# ife18_TS_BMS_Master.net
KiCad netlist of a schematic drawn in Altium Designer
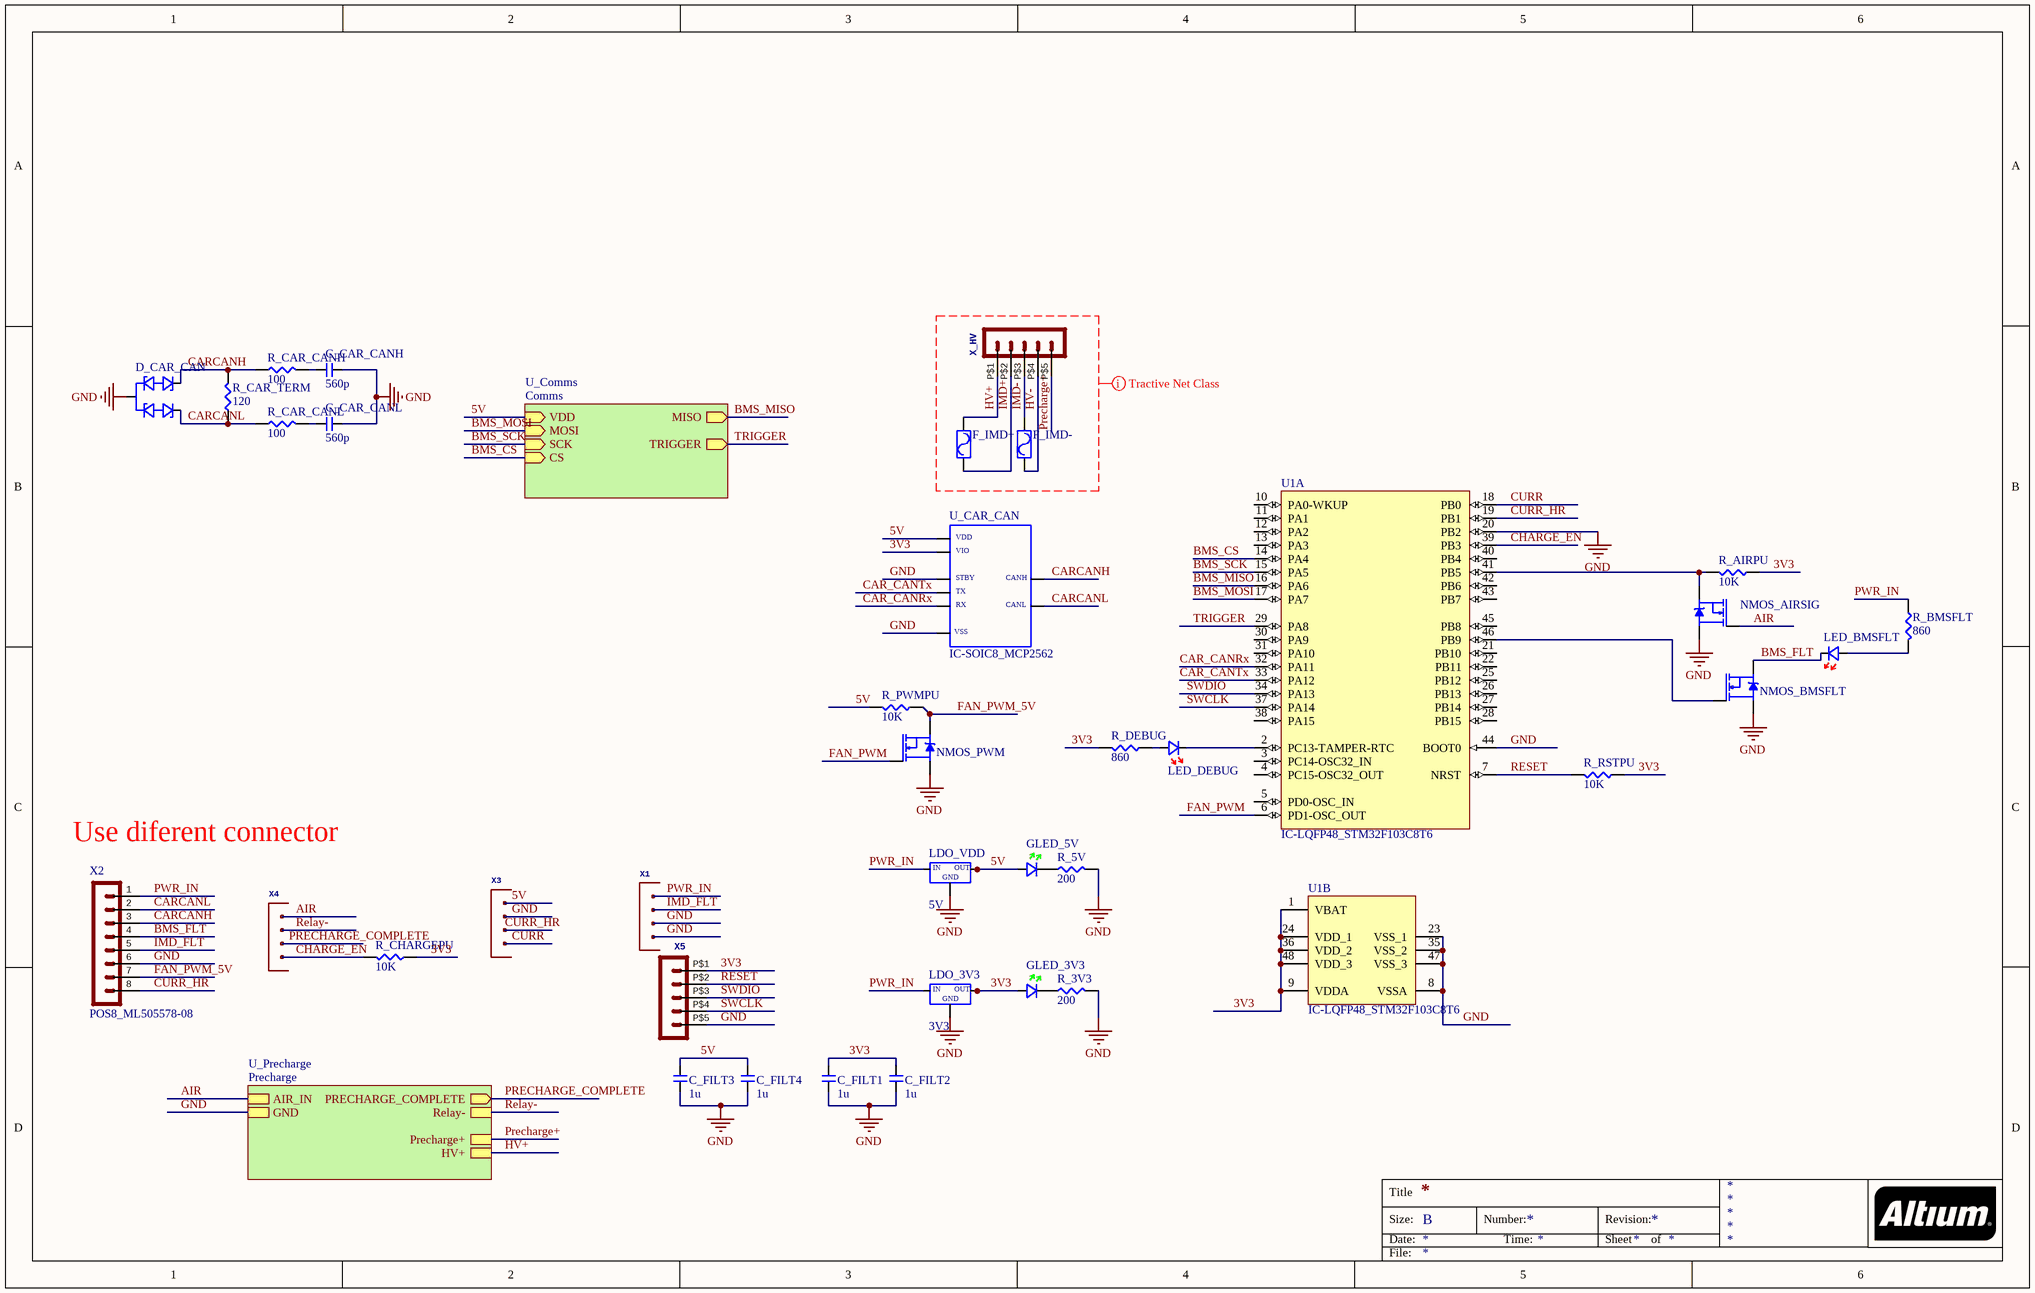
[diagram p0: ife18_TS_BMS_Master.SchDoc]

(export (version "E")
  (design (tool "Eeschema 10.0.6"))
  (components
    (comp (ref "C_CAR_CANH")
      (value "560p")
      (footprint "CAP-0603")
      (libsource (lib "altium-import") (part "root_0_CAP-0603_"))
    )
    (comp (ref "C_CAR_CANL")
      (value "560p")
      (footprint "CAP-0603")
      (libsource (lib "altium-import") (part "root_0_CAP-0603_"))
    )
    (comp (ref "C_FILT1")
      (value "1u")
      (footprint "CAP-0603")
      (libsource (lib "altium-import") (part "root_1_CAP-0603_"))
    )
    (comp (ref "C_FILT2")
      (value "1u")
      (footprint "CAP-0603")
      (libsource (lib "altium-import") (part "root_1_CAP-0603_"))
    )
    (comp (ref "C_FILT3")
      (value "1u")
      (footprint "CAP-0603")
      (libsource (lib "altium-import") (part "root_1_CAP-0603_"))
    )
    (comp (ref "C_FILT4")
      (value "1u")
      (footprint "CAP-0603")
      (libsource (lib "altium-import") (part "root_1_CAP-0603_"))
    )
    (comp (ref "D_CAR_CAN")
      (value "DIODE-SOT23_PESD1CAN")
      (footprint "SOT23")
      (libsource (lib "altium-import") (part "root_0_DIODE-SOT23_PESD1CAN_"))
    )
    (comp (ref "F_IMD+")
      (value "FUSE_885")
      (footprint "FUSE_885")
      (libsource (lib "ife19_Elec_Library") (part "FUSE_885"))
    )
    (comp (ref "F_IMD-")
      (value "FUSE_885")
      (footprint "FUSE_885")
      (libsource (lib "ife19_Elec_Library") (part "FUSE_885"))
    )
    (comp (ref "GLED_3V3")
      (value "~")
      (footprint "LEDGREEN-0603")
      (libsource (lib "altium-import") (part "root_0_LEDGREEN-0603_"))
    )
    (comp (ref "GLED_5V")
      (value "~")
      (footprint "LEDGREEN-0603")
      (libsource (lib "altium-import") (part "root_0_LEDGREEN-0603_"))
    )
    (comp (ref "LDO_3V3")
      (value "3V3")
      (footprint "SOT223")
      (libsource (lib "altium-import") (part "root_0_LDO-SOT223_SPX1117_"))
    )
    (comp (ref "LDO_VDD")
      (value "5V")
      (footprint "SOT223")
      (libsource (lib "altium-import") (part "root_0_LDO-SOT223_SPX1117_"))
    )
    (comp (ref "LED_BMSFLT")
      (value "LEDRED-0603")
      (footprint "LEDRED-0603")
      (libsource (lib "altium-import") (part "root_2_LEDRED-0603_"))
    )
    (comp (ref "LED_DEBUG")
      (value "LEDRED-0603")
      (footprint "LEDRED-0603")
      (libsource (lib "altium-import") (part "root_2_mirrored_LEDRED-0603_"))
    )
    (comp (ref "NMOS_AIRSIG")
      (value "NMOS-SOT23")
      (footprint "SOT23")
      (libsource (lib "altium-import") (part "root_0_NMOS-SOT23_"))
    )
    (comp (ref "NMOS_BMSFLT")
      (value "NMOS-SOT23")
      (footprint "SOT23")
      (libsource (lib "altium-import") (part "root_0_mirrored_NMOS-SOT23_"))
    )
    (comp (ref "NMOS_PWM")
      (value "NMOS-SOT23")
      (footprint "SOT23")
      (libsource (lib "altium-import") (part "root_0_mirrored_NMOS-SOT23_"))
    )
    (comp (ref "R_3V3")
      (value "200")
      (footprint "RES-0603")
      (libsource (lib "altium-import") (part "root_0_RES-0603_"))
    )
    (comp (ref "R_5V")
      (value "200")
      (footprint "RES-0603")
      (libsource (lib "altium-import") (part "root_0_RES-0603_"))
    )
    (comp (ref "R_AIRPU")
      (value "10K")
      (footprint "RES-0603")
      (libsource (lib "altium-import") (part "root_2_RES-0603_"))
    )
    (comp (ref "R_BMSFLT")
      (value "860")
      (footprint "RES-0603")
      (libsource (lib "altium-import") (part "root_1_mirrored_RES-0603_"))
    )
    (comp (ref "R_CAR_CANH")
      (value "100")
      (footprint "RES-0603")
      (libsource (lib "altium-import") (part "root_0_RES-0603_"))
    )
    (comp (ref "R_CAR_CANL")
      (value "100")
      (footprint "RES-0603")
      (libsource (lib "altium-import") (part "root_0_RES-0603_"))
    )
    (comp (ref "R_CAR_TERM")
      (value "120")
      (footprint "RES-0603")
      (libsource (lib "altium-import") (part "root_1_RES-0603_"))
    )
    (comp (ref "R_CHARGEPU")
      (value "10K")
      (footprint "RES-0603")
      (libsource (lib "altium-import") (part "root_2_RES-0603_"))
    )
    (comp (ref "R_DEBUG")
      (value "860")
      (footprint "RES-0603")
      (libsource (lib "altium-import") (part "root_2_RES-0603_"))
    )
    (comp (ref "R_PWMPU")
      (value "10K")
      (footprint "RES-0603")
      (libsource (lib "altium-import") (part "root_2_mirrored_RES-0603_"))
    )
    (comp (ref "R_RSTPU")
      (value "10K")
      (footprint "RES-0603")
      (libsource (lib "altium-import") (part "root_2_RES-0603_"))
    )
    (comp (ref "U1")
      (value "IC-LQFP48_STM32F103C8T6")
      (footprint "STM-LQFP48_M")
      (fields (field (name "PARTNUMBER") "STM32F103C8T6"))
      (libsource (lib "ife19_Elec_Library") (part "IC-LQFP48_STM32F103C8T6"))
    )
    (comp (ref "U_CAR_CAN")
      (value "IC-SOIC8_MCP2562")
      (footprint "SOIC8")
      (libsource (lib "altium-import") (part "root_0_IC-SOIC8_MCP2562_"))
    )
    (comp (ref "X1")
      (value "Molex 505575-04 4 Position 2.00mm pitch connector wire to board connector Datasheet")
      (footprint "505578-04")
      (fields (field (name "LIBRARYNAME") "MOLEX Micro-Lock"))
      (libsource (lib "ife19_Elec_Conn_Library") (part "POS4_ML505578-04"))
    )
    (comp (ref "X2")
      (value "POS8_ML505578-08")
      (footprint "505575-08")
      (fields (field (name "MANUFACTURER") "Molex") (field (name "MANUFACTURER PART NUMBER") "172065-0308"))
      (libsource (lib "ife19_Elec_Conn_Library") (part "POS8_ML505578-08"))
    )
    (comp (ref "X3")
      (value "Molex 505575-04 4 Position 2.00mm pitch connector wire to board connector Datasheet")
      (footprint "505578-04")
      (fields (field (name "LIBRARYNAME") "MOLEX Micro-Lock"))
      (libsource (lib "ife19_Elec_Conn_Library") (part "POS4_ML505578-04"))
    )
    (comp (ref "X4")
      (value "Molex 505575-04 4 Position 2.00mm pitch connector wire to board connector Datasheet")
      (footprint "505578-04")
      (fields (field (name "LIBRARYNAME") "MOLEX Micro-Lock"))
      (libsource (lib "ife19_Elec_Conn_Library") (part "POS4_ML505578-04"))
    )
    (comp (ref "X5")
      (value "~")
      (footprint "POS5_254MM_MALE")
      (libsource (lib "altium-import") (part "root_0_mirrored_POS5_254MM_MALE_"))
    )
    (comp (ref "X_HV")
      (value "Molex - Micro-Fit 3.0 Series connector,  3.00mm (0.118\") pitch header, 5 positions.")
      (footprint "43650-0524")
      (libsource (lib "ife19_Elec_Conn_Library") (part "POS5_MF43650-0524"))
    )
  )
  (nets
    (net (code "1") (name "/3V3") (class "Default")
      (node (ref "C_FILT1") (pin "2") (pinfunction "2_2") (pintype "passive"))
      (node (ref "C_FILT2") (pin "2") (pinfunction "2_2") (pintype "passive"))
      (node (ref "GLED_3V3") (pin "A") (pinfunction "A_A") (pintype "passive"))
      (node (ref "LDO_3V3") (pin "2") (pinfunction "2_2") (pintype "passive"))
      (node (ref "LDO_3V3") (pin "4") (pinfunction "4_4") (pintype "passive"))
      (node (ref "R_AIRPU") (pin "1") (pinfunction "1_1") (pintype "passive"))
      (node (ref "R_CHARGEPU") (pin "1") (pinfunction "1_1") (pintype "passive"))
      (node (ref "R_DEBUG") (pin "2") (pinfunction "2_2") (pintype "passive"))
      (node (ref "R_RSTPU") (pin "1") (pinfunction "1_1") (pintype "passive"))
      (node (ref "U1") (pin "1") (pinfunction "VBAT_1") (pintype "power_in"))
      (node (ref "U1") (pin "24") (pinfunction "VDD_1_24") (pintype "power_in"))
      (node (ref "U1") (pin "36") (pinfunction "VDD_2_36") (pintype "power_in"))
      (node (ref "U1") (pin "48") (pinfunction "VDD_3_48") (pintype "power_in"))
      (node (ref "U1") (pin "9") (pinfunction "VDDA_9") (pintype "power_in"))
      (node (ref "U_CAR_CAN") (pin "5") (pinfunction "5_5") (pintype "passive"))
      (node (ref "X5") (pin "P$1") (pinfunction "1_P$1") (pintype "passive"))
    )
    (net (code "2") (name "/5V") (class "Default")
      (node (ref "C_FILT3") (pin "2") (pinfunction "2_2") (pintype "passive"))
      (node (ref "C_FILT4") (pin "2") (pinfunction "2_2") (pintype "passive"))
      (node (ref "GLED_5V") (pin "A") (pinfunction "A_A") (pintype "passive"))
      (node (ref "LDO_VDD") (pin "2") (pinfunction "2_2") (pintype "passive"))
      (node (ref "LDO_VDD") (pin "4") (pinfunction "4_4") (pintype "passive"))
      (node (ref "R_PWMPU") (pin "1") (pinfunction "1_1") (pintype "passive"))
      (node (ref "U_CAR_CAN") (pin "3") (pinfunction "3_3") (pintype "passive"))
      (node (ref "X3") (pin "1") (pinfunction "1_1") (pintype "passive"))
    )
    (net (code "3") (name "/AIR") (class "Default")
      (node (ref "NMOS_AIRSIG") (pin "1") (pinfunction "G_1") (pintype "passive"))
      (node (ref "X4") (pin "1") (pinfunction "1_1") (pintype "passive"))
    )
    (net (code "4") (name "/BMS_CS") (class "Default")
      (node (ref "U1") (pin "14") (pinfunction "PA4_14") (pintype "bidirectional"))
    )
    (net (code "5") (name "/BMS_FLT") (class "Default")
      (node (ref "LED_BMSFLT") (pin "K") (pinfunction "K_K") (pintype "passive"))
      (node (ref "NMOS_BMSFLT") (pin "3") (pinfunction "D_3") (pintype "passive"))
      (node (ref "X2") (pin "4") (pinfunction "4_4") (pintype "passive"))
    )
    (net (code "6") (name "/BMS_MISO") (class "Default")
      (node (ref "U1") (pin "16") (pinfunction "PA6_16") (pintype "bidirectional"))
    )
    (net (code "7") (name "/BMS_MOSI") (class "Default")
      (node (ref "U1") (pin "17") (pinfunction "PA7_17") (pintype "bidirectional"))
    )
    (net (code "8") (name "/BMS_SCK") (class "Default")
      (node (ref "U1") (pin "15") (pinfunction "PA5_15") (pintype "bidirectional"))
    )
    (net (code "9") (name "/CARCANH") (class "Default")
      (node (ref "D_CAR_CAN") (pin "2") (pinfunction "CAN2_2") (pintype "passive"))
      (node (ref "R_CAR_CANH") (pin "1") (pinfunction "1_1") (pintype "passive"))
      (node (ref "R_CAR_TERM") (pin "2") (pinfunction "2_2") (pintype "passive"))
      (node (ref "U_CAR_CAN") (pin "7") (pinfunction "7_7") (pintype "passive"))
      (node (ref "X2") (pin "3") (pinfunction "3_3") (pintype "passive"))
    )
    (net (code "10") (name "/CARCANL") (class "Default")
      (node (ref "D_CAR_CAN") (pin "1") (pinfunction "CAN1_1") (pintype "passive"))
      (node (ref "R_CAR_CANL") (pin "1") (pinfunction "1_1") (pintype "passive"))
      (node (ref "R_CAR_TERM") (pin "1") (pinfunction "1_1") (pintype "passive"))
      (node (ref "U_CAR_CAN") (pin "6") (pinfunction "6_6") (pintype "passive"))
      (node (ref "X2") (pin "2") (pinfunction "2_2") (pintype "passive"))
    )
    (net (code "11") (name "/CAR_CANRx") (class "Default")
      (node (ref "U1") (pin "32") (pinfunction "PA11_32") (pintype "bidirectional"))
      (node (ref "U_CAR_CAN") (pin "4") (pinfunction "4_4") (pintype "passive"))
    )
    (net (code "12") (name "/CAR_CANTx") (class "Default")
      (node (ref "U1") (pin "33") (pinfunction "PA12_33") (pintype "bidirectional"))
      (node (ref "U_CAR_CAN") (pin "1") (pinfunction "1_1") (pintype "passive"))
    )
    (net (code "13") (name "/CHARGE_EN") (class "Default")
      (node (ref "R_CHARGEPU") (pin "2") (pinfunction "2_2") (pintype "passive"))
      (node (ref "U1") (pin "39") (pinfunction "PB3_39") (pintype "bidirectional"))
      (node (ref "X4") (pin "4") (pinfunction "4_4") (pintype "passive"))
    )
    (net (code "14") (name "/CURR") (class "Default")
      (node (ref "U1") (pin "18") (pinfunction "PB0_18") (pintype "bidirectional"))
      (node (ref "X3") (pin "4") (pinfunction "4_4") (pintype "passive"))
    )
    (net (code "15") (name "/CURR_HR") (class "Default")
      (node (ref "U1") (pin "19") (pinfunction "PB1_19") (pintype "bidirectional"))
      (node (ref "X2") (pin "8") (pinfunction "8_8") (pintype "passive"))
      (node (ref "X3") (pin "3") (pinfunction "3_3") (pintype "passive"))
    )
    (net (code "16") (name "/FAN_PWM") (class "Default")
      (node (ref "NMOS_PWM") (pin "1") (pinfunction "G_1") (pintype "passive"))
      (node (ref "U1") (pin "6") (pinfunction "PD1-OSC_OUT_6") (pintype "bidirectional"))
    )
    (net (code "17") (name "/FAN_PWM_5V") (class "Default")
      (node (ref "NMOS_PWM") (pin "3") (pinfunction "D_3") (pintype "passive"))
      (node (ref "R_PWMPU") (pin "2") (pinfunction "2_2") (pintype "passive"))
      (node (ref "X2") (pin "7") (pinfunction "7_7") (pintype "passive"))
    )
    (net (code "18") (name "/HV+") (class "Default")
      (node (ref "F_IMD+") (pin "1") (pinfunction "1_1") (pintype "passive"))
      (node (ref "X_HV") (pin "P$1") (pinfunction "1_P$1") (pintype "passive"))
    )
    (net (code "19") (name "/HV-") (class "Default")
      (node (ref "F_IMD-") (pin "2") (pinfunction "2_2") (pintype "passive"))
      (node (ref "X_HV") (pin "P$4") (pinfunction "4_P$4") (pintype "passive"))
    )
    (net (code "20") (name "/IMD+") (class "Default")
      (node (ref "F_IMD+") (pin "2") (pinfunction "2_2") (pintype "passive"))
      (node (ref "X_HV") (pin "P$2") (pinfunction "2_P$2") (pintype "passive"))
    )
    (net (code "21") (name "/IMD-") (class "Default")
      (node (ref "F_IMD-") (pin "1") (pinfunction "1_1") (pintype "passive"))
      (node (ref "X_HV") (pin "P$3") (pinfunction "3_P$3") (pintype "passive"))
    )
    (net (code "22") (name "/IMD_FLT") (class "Default")
      (node (ref "X1") (pin "2") (pinfunction "2_2") (pintype "passive"))
      (node (ref "X2") (pin "5") (pinfunction "5_5") (pintype "passive"))
    )
    (net (code "23") (name "/PRECHARGE_COMPLETE") (class "Default")
      (node (ref "X4") (pin "3") (pinfunction "3_3") (pintype "passive"))
    )
    (net (code "24") (name "/PWR_IN") (class "Default")
      (node (ref "LDO_3V3") (pin "3") (pinfunction "3_3") (pintype "passive"))
      (node (ref "LDO_VDD") (pin "3") (pinfunction "3_3") (pintype "passive"))
      (node (ref "R_BMSFLT") (pin "2") (pinfunction "2_2") (pintype "passive"))
      (node (ref "X1") (pin "1") (pinfunction "1_1") (pintype "passive"))
      (node (ref "X2") (pin "1") (pinfunction "1_1") (pintype "passive"))
    )
    (net (code "25") (name "/Precharge+") (class "Default")
      (node (ref "X_HV") (pin "P$5") (pinfunction "5_P$5") (pintype "passive"))
    )
    (net (code "26") (name "/RESET") (class "Default")
      (node (ref "R_RSTPU") (pin "2") (pinfunction "2_2") (pintype "passive"))
      (node (ref "U1") (pin "7") (pinfunction "NRST_7") (pintype "bidirectional"))
      (node (ref "X5") (pin "P$2") (pinfunction "2_P$2") (pintype "passive"))
    )
    (net (code "27") (name "/Relay-") (class "Default")
      (node (ref "X4") (pin "2") (pinfunction "2_2") (pintype "passive"))
    )
    (net (code "28") (name "/SWCLK") (class "Default")
      (node (ref "U1") (pin "37") (pinfunction "PA14_37") (pintype "bidirectional"))
      (node (ref "X5") (pin "P$4") (pinfunction "4_P$4") (pintype "passive"))
    )
    (net (code "29") (name "/SWDIO") (class "Default")
      (node (ref "U1") (pin "34") (pinfunction "PA13_34") (pintype "bidirectional"))
      (node (ref "X5") (pin "P$3") (pinfunction "3_P$3") (pintype "passive"))
    )
    (net (code "30") (name "/TRIGGER") (class "Default")
      (node (ref "U1") (pin "29") (pinfunction "PA8_29") (pintype "bidirectional"))
    )
    (net (code "31") (name "GND") (class "Default")
      (node (ref "C_CAR_CANH") (pin "2") (pinfunction "2_2") (pintype "passive"))
      (node (ref "C_CAR_CANL") (pin "2") (pinfunction "2_2") (pintype "passive"))
      (node (ref "C_FILT1") (pin "1") (pinfunction "1_1") (pintype "passive"))
      (node (ref "C_FILT2") (pin "1") (pinfunction "1_1") (pintype "passive"))
      (node (ref "C_FILT3") (pin "1") (pinfunction "1_1") (pintype "passive"))
      (node (ref "C_FILT4") (pin "1") (pinfunction "1_1") (pintype "passive"))
      (node (ref "D_CAR_CAN") (pin "3") (pinfunction "G_3") (pintype "passive"))
      (node (ref "LDO_3V3") (pin "1") (pinfunction "1_1") (pintype "passive"))
      (node (ref "LDO_VDD") (pin "1") (pinfunction "1_1") (pintype "passive"))
      (node (ref "NMOS_AIRSIG") (pin "2") (pinfunction "S_2") (pintype "passive"))
      (node (ref "NMOS_BMSFLT") (pin "2") (pinfunction "S_2") (pintype "passive"))
      (node (ref "NMOS_PWM") (pin "2") (pinfunction "S_2") (pintype "passive"))
      (node (ref "R_3V3") (pin "2") (pinfunction "2_2") (pintype "passive"))
      (node (ref "R_5V") (pin "2") (pinfunction "2_2") (pintype "passive"))
      (node (ref "U1") (pin "20") (pinfunction "PB2_20") (pintype "bidirectional"))
      (node (ref "U1") (pin "23") (pinfunction "VSS_1_23") (pintype "power_in"))
      (node (ref "U1") (pin "35") (pinfunction "VSS_2_35") (pintype "power_in"))
      (node (ref "U1") (pin "44") (pinfunction "BOOT0_44") (pintype "input"))
      (node (ref "U1") (pin "47") (pinfunction "VSS_3_47") (pintype "power_in"))
      (node (ref "U1") (pin "8") (pinfunction "VSSA_8") (pintype "power_in"))
      (node (ref "U_CAR_CAN") (pin "2") (pinfunction "2_2") (pintype "passive"))
      (node (ref "U_CAR_CAN") (pin "8") (pinfunction "8_8") (pintype "passive"))
      (node (ref "X1") (pin "3") (pinfunction "3_3") (pintype "passive"))
      (node (ref "X1") (pin "4") (pinfunction "4_4") (pintype "passive"))
      (node (ref "X2") (pin "6") (pinfunction "6_6") (pintype "passive"))
      (node (ref "X3") (pin "2") (pinfunction "2_2") (pintype "passive"))
      (node (ref "X5") (pin "P$5") (pinfunction "5_P$5") (pintype "passive"))
    )
    (net (code "32") (name "Net-(C_CAR_CANH-Pad1)") (class "Default")
      (node (ref "C_CAR_CANH") (pin "1") (pinfunction "1_1") (pintype "passive"))
      (node (ref "R_CAR_CANH") (pin "2") (pinfunction "2_2") (pintype "passive"))
    )
    (net (code "33") (name "Net-(C_CAR_CANL-Pad1)") (class "Default")
      (node (ref "C_CAR_CANL") (pin "1") (pinfunction "1_1") (pintype "passive"))
      (node (ref "R_CAR_CANL") (pin "2") (pinfunction "2_2") (pintype "passive"))
    )
    (net (code "34") (name "Net-(GLED_3V3-PadK)") (class "Default")
      (node (ref "GLED_3V3") (pin "K") (pinfunction "K_K") (pintype "passive"))
      (node (ref "R_3V3") (pin "1") (pinfunction "1_1") (pintype "passive"))
    )
    (net (code "35") (name "Net-(GLED_5V-PadK)") (class "Default")
      (node (ref "GLED_5V") (pin "K") (pinfunction "K_K") (pintype "passive"))
      (node (ref "R_5V") (pin "1") (pinfunction "1_1") (pintype "passive"))
    )
    (net (code "36") (name "Net-(LED_BMSFLT-PadA)") (class "Default")
      (node (ref "LED_BMSFLT") (pin "A") (pinfunction "A_A") (pintype "passive"))
      (node (ref "R_BMSFLT") (pin "1") (pinfunction "1_1") (pintype "passive"))
    )
    (net (code "37") (name "Net-(LED_DEBUG-PadA)") (class "Default")
      (node (ref "LED_DEBUG") (pin "A") (pinfunction "A_A") (pintype "passive"))
      (node (ref "R_DEBUG") (pin "1") (pinfunction "1_1") (pintype "passive"))
    )
    (net (code "38") (name "Net-(NMOS_AIRSIG-D)") (class "Default")
      (node (ref "NMOS_AIRSIG") (pin "3") (pinfunction "D_3") (pintype "passive"))
      (node (ref "R_AIRPU") (pin "2") (pinfunction "2_2") (pintype "passive"))
      (node (ref "U1") (pin "41") (pinfunction "PB5_41") (pintype "bidirectional"))
    )
    (net (code "39") (name "Net-(NMOS_BMSFLT-G)") (class "Default")
      (node (ref "NMOS_BMSFLT") (pin "1") (pinfunction "G_1") (pintype "passive"))
      (node (ref "U1") (pin "46") (pinfunction "PB9_46") (pintype "bidirectional"))
    )
    (net (code "40") (name "Net-(U1A-PC13-TAMPER-RTC)") (class "Default")
      (node (ref "LED_DEBUG") (pin "K") (pinfunction "K_K") (pintype "passive"))
      (node (ref "U1") (pin "2") (pinfunction "PC13-TAMPER-RTC_2") (pintype "bidirectional"))
    )
    (net (code "41") (name "unconnected-(U1A-PA0-WKUP-Pad10)") (class "Default")
      (node (ref "U1") (pin "10") (pinfunction "PA0-WKUP_10") (pintype "bidirectional"))
    )
    (net (code "42") (name "unconnected-(U1A-PA1-Pad11)") (class "Default")
      (node (ref "U1") (pin "11") (pinfunction "PA1_11") (pintype "bidirectional"))
    )
    (net (code "43") (name "unconnected-(U1A-PA2-Pad12)") (class "Default")
      (node (ref "U1") (pin "12") (pinfunction "PA2_12") (pintype "bidirectional"))
    )
    (net (code "44") (name "unconnected-(U1A-PA3-Pad13)") (class "Default")
      (node (ref "U1") (pin "13") (pinfunction "PA3_13") (pintype "bidirectional"))
    )
    (net (code "45") (name "unconnected-(U1A-PA9-Pad30)") (class "Default")
      (node (ref "U1") (pin "30") (pinfunction "PA9_30") (pintype "bidirectional"))
    )
    (net (code "46") (name "unconnected-(U1A-PA10-Pad31)") (class "Default")
      (node (ref "U1") (pin "31") (pinfunction "PA10_31") (pintype "bidirectional"))
    )
    (net (code "47") (name "unconnected-(U1A-PA15-Pad38)") (class "Default")
      (node (ref "U1") (pin "38") (pinfunction "PA15_38") (pintype "bidirectional"))
    )
    (net (code "48") (name "unconnected-(U1A-PB4-Pad40)") (class "Default")
      (node (ref "U1") (pin "40") (pinfunction "PB4_40") (pintype "bidirectional"))
    )
    (net (code "49") (name "unconnected-(U1A-PB6-Pad42)") (class "Default")
      (node (ref "U1") (pin "42") (pinfunction "PB6_42") (pintype "bidirectional"))
    )
    (net (code "50") (name "unconnected-(U1A-PB7-Pad43)") (class "Default")
      (node (ref "U1") (pin "43") (pinfunction "PB7_43") (pintype "bidirectional"))
    )
    (net (code "51") (name "unconnected-(U1A-PB8-Pad45)") (class "Default")
      (node (ref "U1") (pin "45") (pinfunction "PB8_45") (pintype "bidirectional"))
    )
    (net (code "52") (name "unconnected-(U1A-PB10-Pad21)") (class "Default")
      (node (ref "U1") (pin "21") (pinfunction "PB10_21") (pintype "bidirectional"))
    )
    (net (code "53") (name "unconnected-(U1A-PB11-Pad22)") (class "Default")
      (node (ref "U1") (pin "22") (pinfunction "PB11_22") (pintype "bidirectional"))
    )
    (net (code "54") (name "unconnected-(U1A-PB12-Pad25)") (class "Default")
      (node (ref "U1") (pin "25") (pinfunction "PB12_25") (pintype "bidirectional"))
    )
    (net (code "55") (name "unconnected-(U1A-PB13-Pad26)") (class "Default")
      (node (ref "U1") (pin "26") (pinfunction "PB13_26") (pintype "bidirectional"))
    )
    (net (code "56") (name "unconnected-(U1A-PB14-Pad27)") (class "Default")
      (node (ref "U1") (pin "27") (pinfunction "PB14_27") (pintype "bidirectional"))
    )
    (net (code "57") (name "unconnected-(U1A-PB15-Pad28)") (class "Default")
      (node (ref "U1") (pin "28") (pinfunction "PB15_28") (pintype "bidirectional"))
    )
    (net (code "58") (name "unconnected-(U1A-PC14-OSC32_IN-Pad3)") (class "Default")
      (node (ref "U1") (pin "3") (pinfunction "PC14-OSC32_IN_3") (pintype "bidirectional"))
    )
    (net (code "59") (name "unconnected-(U1A-PC15-OSC32_OUT-Pad4)") (class "Default")
      (node (ref "U1") (pin "4") (pinfunction "PC15-OSC32_OUT_4") (pintype "bidirectional"))
    )
    (net (code "60") (name "unconnected-(U1A-PD0-OSC_IN-Pad5)") (class "Default")
      (node (ref "U1") (pin "5") (pinfunction "PD0-OSC_IN_5") (pintype "bidirectional"))
    )
  )
)
